# Input_v1_1.net
KiCad netlist of a schematic drawn in EAGLE
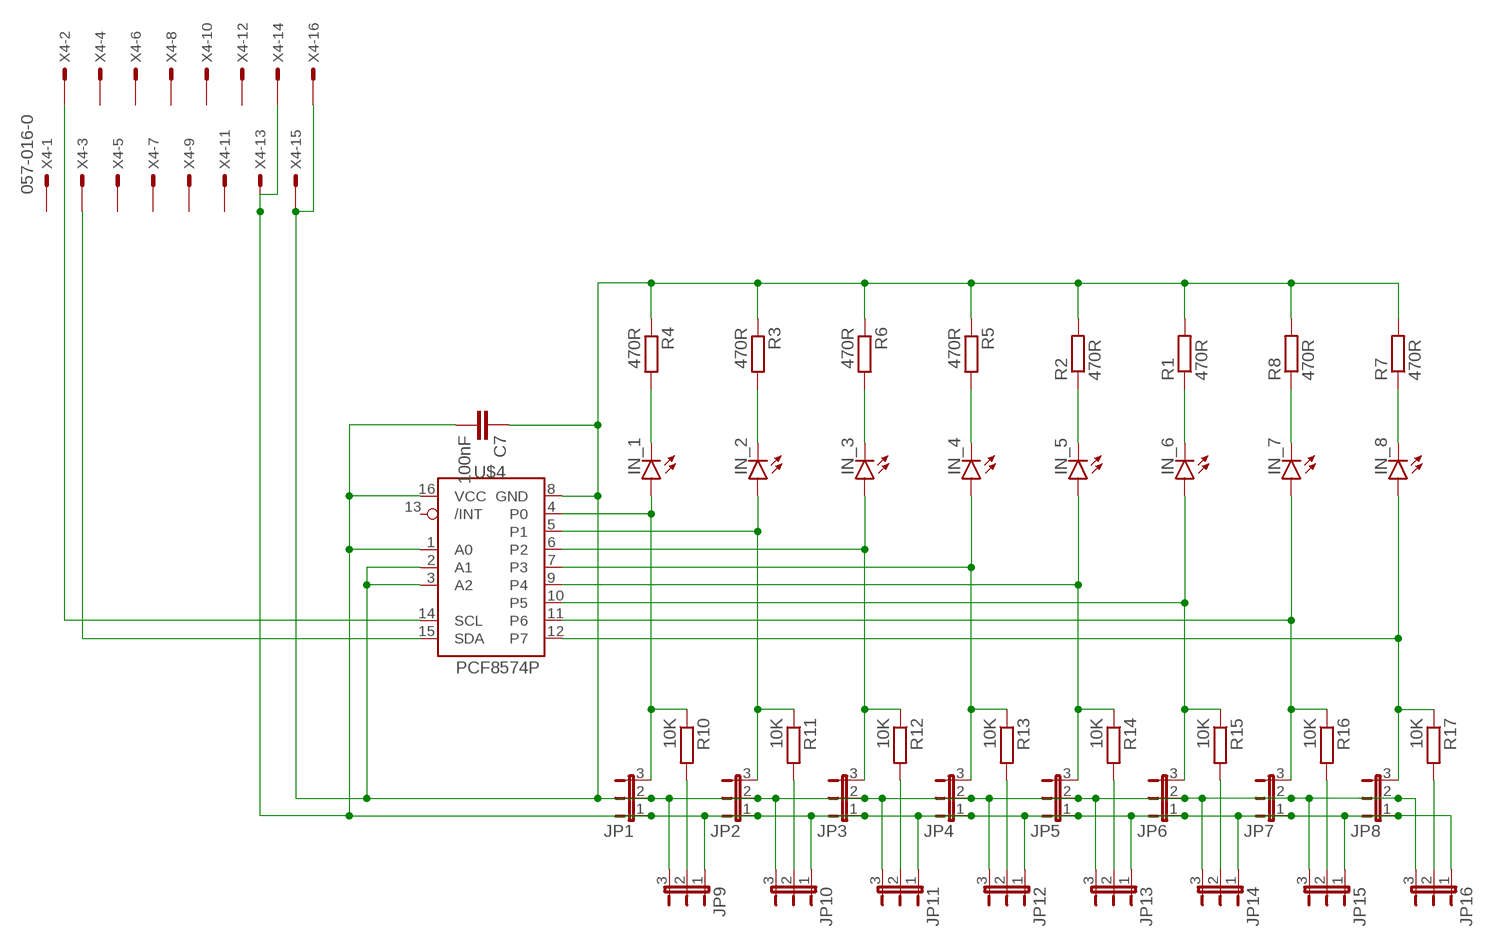
[diagram p0: schematic, sheet 1]

(export (version "E")
  (design (tool "Eeschema 10.0.6"))
  (components
    (comp (ref "C7")
      (value "100nF")
      (footprint "eagle-import:C025-024X044")
      (libsource (lib "eagle-import") (part "C-EU025-024X044"))
    )
    (comp (ref "IN_1")
      (value "LED3MM")
      (footprint "eagle-import:LED3MM")
      (libsource (lib "eagle-import") (part "LED3MM"))
    )
    (comp (ref "IN_2")
      (value "LED3MM")
      (footprint "eagle-import:LED3MM")
      (libsource (lib "eagle-import") (part "LED3MM"))
    )
    (comp (ref "IN_3")
      (value "LED3MM")
      (footprint "eagle-import:LED3MM")
      (libsource (lib "eagle-import") (part "LED3MM"))
    )
    (comp (ref "IN_4")
      (value "LED3MM")
      (footprint "eagle-import:LED3MM")
      (libsource (lib "eagle-import") (part "LED3MM"))
    )
    (comp (ref "IN_5")
      (value "LED3MM")
      (footprint "eagle-import:LED3MM")
      (libsource (lib "eagle-import") (part "LED3MM"))
    )
    (comp (ref "IN_6")
      (value "LED3MM")
      (footprint "eagle-import:LED3MM")
      (libsource (lib "eagle-import") (part "LED3MM"))
    )
    (comp (ref "IN_7")
      (value "LED3MM")
      (footprint "eagle-import:LED3MM")
      (libsource (lib "eagle-import") (part "LED3MM"))
    )
    (comp (ref "IN_8")
      (value "LED3MM")
      (footprint "eagle-import:LED3MM")
      (libsource (lib "eagle-import") (part "LED3MM"))
    )
    (comp (ref "JP1")
      (value "JP2E")
      (footprint "eagle-import:JP2")
      (libsource (lib "eagle-import") (part "JP2E"))
    )
    (comp (ref "JP2")
      (value "JP2E")
      (footprint "eagle-import:JP2")
      (libsource (lib "eagle-import") (part "JP2E"))
    )
    (comp (ref "JP3")
      (value "JP2E")
      (footprint "eagle-import:JP2")
      (libsource (lib "eagle-import") (part "JP2E"))
    )
    (comp (ref "JP4")
      (value "JP2E")
      (footprint "eagle-import:JP2")
      (libsource (lib "eagle-import") (part "JP2E"))
    )
    (comp (ref "JP5")
      (value "JP2E")
      (footprint "eagle-import:JP2")
      (libsource (lib "eagle-import") (part "JP2E"))
    )
    (comp (ref "JP6")
      (value "JP2E")
      (footprint "eagle-import:JP2")
      (libsource (lib "eagle-import") (part "JP2E"))
    )
    (comp (ref "JP7")
      (value "JP2E")
      (footprint "eagle-import:JP2")
      (libsource (lib "eagle-import") (part "JP2E"))
    )
    (comp (ref "JP8")
      (value "JP2E")
      (footprint "eagle-import:JP2")
      (libsource (lib "eagle-import") (part "JP2E"))
    )
    (comp (ref "JP9")
      (value "JP2E")
      (footprint "eagle-import:JP2")
      (libsource (lib "eagle-import") (part "JP2E"))
    )
    (comp (ref "JP10")
      (value "JP2E")
      (footprint "eagle-import:JP2")
      (libsource (lib "eagle-import") (part "JP2E"))
    )
    (comp (ref "JP11")
      (value "JP2E")
      (footprint "eagle-import:JP2")
      (libsource (lib "eagle-import") (part "JP2E"))
    )
    (comp (ref "JP12")
      (value "JP2E")
      (footprint "eagle-import:JP2")
      (libsource (lib "eagle-import") (part "JP2E"))
    )
    (comp (ref "JP13")
      (value "JP2E")
      (footprint "eagle-import:JP2")
      (libsource (lib "eagle-import") (part "JP2E"))
    )
    (comp (ref "JP14")
      (value "JP2E")
      (footprint "eagle-import:JP2")
      (libsource (lib "eagle-import") (part "JP2E"))
    )
    (comp (ref "JP15")
      (value "JP2E")
      (footprint "eagle-import:JP2")
      (libsource (lib "eagle-import") (part "JP2E"))
    )
    (comp (ref "JP16")
      (value "JP2E")
      (footprint "eagle-import:JP2")
      (libsource (lib "eagle-import") (part "JP2E"))
    )
    (comp (ref "R1")
      (value "470R")
      (footprint "eagle-import:0309_10")
      (libsource (lib "eagle-import") (part "R-EU_0309/10"))
    )
    (comp (ref "R2")
      (value "470R")
      (footprint "eagle-import:0309_10")
      (libsource (lib "eagle-import") (part "R-EU_0309/10"))
    )
    (comp (ref "R3")
      (value "470R")
      (footprint "eagle-import:0309_10")
      (libsource (lib "eagle-import") (part "R-EU_0309/10"))
    )
    (comp (ref "R4")
      (value "470R")
      (footprint "eagle-import:0309_10")
      (libsource (lib "eagle-import") (part "R-EU_0309/10"))
    )
    (comp (ref "R5")
      (value "470R")
      (footprint "eagle-import:0309_10")
      (libsource (lib "eagle-import") (part "R-EU_0309/10"))
    )
    (comp (ref "R6")
      (value "470R")
      (footprint "eagle-import:0309_10")
      (libsource (lib "eagle-import") (part "R-EU_0309/10"))
    )
    (comp (ref "R7")
      (value "470R")
      (footprint "eagle-import:0309_10")
      (libsource (lib "eagle-import") (part "R-EU_0309/10"))
    )
    (comp (ref "R8")
      (value "470R")
      (footprint "eagle-import:0309_10")
      (libsource (lib "eagle-import") (part "R-EU_0309/10"))
    )
    (comp (ref "R10")
      (value "10K")
      (footprint "eagle-import:0309_10")
      (libsource (lib "eagle-import") (part "R-EU_0309/10"))
    )
    (comp (ref "R11")
      (value "10K")
      (footprint "eagle-import:0309_10")
      (libsource (lib "eagle-import") (part "R-EU_0309/10"))
    )
    (comp (ref "R12")
      (value "10K")
      (footprint "eagle-import:0309_10")
      (libsource (lib "eagle-import") (part "R-EU_0309/10"))
    )
    (comp (ref "R13")
      (value "10K")
      (footprint "eagle-import:0309_10")
      (libsource (lib "eagle-import") (part "R-EU_0309/10"))
    )
    (comp (ref "R14")
      (value "10K")
      (footprint "eagle-import:0309_10")
      (libsource (lib "eagle-import") (part "R-EU_0309/10"))
    )
    (comp (ref "R15")
      (value "10K")
      (footprint "eagle-import:0309_10")
      (libsource (lib "eagle-import") (part "R-EU_0309/10"))
    )
    (comp (ref "R16")
      (value "10K")
      (footprint "eagle-import:0309_10")
      (libsource (lib "eagle-import") (part "R-EU_0309/10"))
    )
    (comp (ref "R17")
      (value "10K")
      (footprint "eagle-import:0309_10")
      (libsource (lib "eagle-import") (part "R-EU_0309/10"))
    )
    (comp (ref "U$4")
      (value "PCF8574P")
      (footprint "eagle-import:DIL16")
      (libsource (lib "eagle-import") (part "PCF8574P"))
    )
    (comp (ref "X4")
      (value "057-016-0")
      (footprint "eagle-import:057-016-0")
      (libsource (lib "eagle-import") (part "057-016-0"))
    )
  )
  (nets
    (net (code "1") (name "Net-(IN_1-C)") (class "Default")
      (node (ref "IN_1") (pin "K") (pinfunction "C_K") (pintype "passive"))
      (node (ref "R4") (pin "2") (pinfunction "2_2") (pintype "passive"))
    )
    (net (code "2") (name "Net-(IN_2-C)") (class "Default")
      (node (ref "IN_2") (pin "K") (pinfunction "C_K") (pintype "passive"))
      (node (ref "R3") (pin "2") (pinfunction "2_2") (pintype "passive"))
    )
    (net (code "3") (name "Net-(IN_3-C)") (class "Default")
      (node (ref "IN_3") (pin "K") (pinfunction "C_K") (pintype "passive"))
      (node (ref "R6") (pin "2") (pinfunction "2_2") (pintype "passive"))
    )
    (net (code "4") (name "Net-(IN_4-C)") (class "Default")
      (node (ref "IN_4") (pin "K") (pinfunction "C_K") (pintype "passive"))
      (node (ref "R5") (pin "2") (pinfunction "2_2") (pintype "passive"))
    )
    (net (code "5") (name "Net-(IN_5-C)") (class "Default")
      (node (ref "IN_5") (pin "K") (pinfunction "C_K") (pintype "passive"))
      (node (ref "R2") (pin "1") (pinfunction "1_1") (pintype "passive"))
    )
    (net (code "6") (name "Net-(IN_6-C)") (class "Default")
      (node (ref "IN_6") (pin "K") (pinfunction "C_K") (pintype "passive"))
      (node (ref "R1") (pin "1") (pinfunction "1_1") (pintype "passive"))
    )
    (net (code "7") (name "Net-(IN_7-C)") (class "Default")
      (node (ref "IN_7") (pin "K") (pinfunction "C_K") (pintype "passive"))
      (node (ref "R8") (pin "1") (pinfunction "1_1") (pintype "passive"))
    )
    (net (code "8") (name "Net-(IN_8-C)") (class "Default")
      (node (ref "IN_8") (pin "K") (pinfunction "C_K") (pintype "passive"))
      (node (ref "R7") (pin "1") (pinfunction "1_1") (pintype "passive"))
    )
    (net (code "9") (name "Net-(JP9-Pad2)") (class "Default")
      (node (ref "JP9") (pin "2") (pinfunction "2_2") (pintype "passive"))
      (node (ref "R10") (pin "2") (pinfunction "2_2") (pintype "passive"))
    )
    (net (code "10") (name "Net-(JP10-Pad2)") (class "Default")
      (node (ref "JP10") (pin "2") (pinfunction "2_2") (pintype "passive"))
      (node (ref "R11") (pin "2") (pinfunction "2_2") (pintype "passive"))
    )
    (net (code "11") (name "Net-(JP11-Pad2)") (class "Default")
      (node (ref "JP11") (pin "2") (pinfunction "2_2") (pintype "passive"))
      (node (ref "R12") (pin "2") (pinfunction "2_2") (pintype "passive"))
    )
    (net (code "12") (name "Net-(JP12-Pad2)") (class "Default")
      (node (ref "JP12") (pin "2") (pinfunction "2_2") (pintype "passive"))
      (node (ref "R13") (pin "2") (pinfunction "2_2") (pintype "passive"))
    )
    (net (code "13") (name "Net-(JP13-Pad2)") (class "Default")
      (node (ref "JP13") (pin "2") (pinfunction "2_2") (pintype "passive"))
      (node (ref "R14") (pin "2") (pinfunction "2_2") (pintype "passive"))
    )
    (net (code "14") (name "Net-(JP14-Pad2)") (class "Default")
      (node (ref "JP14") (pin "2") (pinfunction "2_2") (pintype "passive"))
      (node (ref "R15") (pin "2") (pinfunction "2_2") (pintype "passive"))
    )
    (net (code "15") (name "Net-(JP15-Pad2)") (class "Default")
      (node (ref "JP15") (pin "2") (pinfunction "2_2") (pintype "passive"))
      (node (ref "R16") (pin "2") (pinfunction "2_2") (pintype "passive"))
    )
    (net (code "16") (name "Net-(JP16-Pad2)") (class "Default")
      (node (ref "JP16") (pin "2") (pinfunction "2_2") (pintype "passive"))
      (node (ref "R17") (pin "2") (pinfunction "2_2") (pintype "passive"))
    )
    (net (code "17") (name "Net-(U$4-A0)") (class "Default")
      (node (ref "C7") (pin "2") (pinfunction "2_2") (pintype "passive"))
      (node (ref "JP1") (pin "1") (pinfunction "1_1") (pintype "passive"))
      (node (ref "JP10") (pin "1") (pinfunction "1_1") (pintype "passive"))
      (node (ref "JP11") (pin "1") (pinfunction "1_1") (pintype "passive"))
      (node (ref "JP12") (pin "1") (pinfunction "1_1") (pintype "passive"))
      (node (ref "JP13") (pin "1") (pinfunction "1_1") (pintype "passive"))
      (node (ref "JP14") (pin "1") (pinfunction "1_1") (pintype "passive"))
      (node (ref "JP15") (pin "1") (pinfunction "1_1") (pintype "passive"))
      (node (ref "JP16") (pin "1") (pinfunction "1_1") (pintype "passive"))
      (node (ref "JP2") (pin "1") (pinfunction "1_1") (pintype "passive"))
      (node (ref "JP3") (pin "1") (pinfunction "1_1") (pintype "passive"))
      (node (ref "JP4") (pin "1") (pinfunction "1_1") (pintype "passive"))
      (node (ref "JP5") (pin "1") (pinfunction "1_1") (pintype "passive"))
      (node (ref "JP6") (pin "1") (pinfunction "1_1") (pintype "passive"))
      (node (ref "JP7") (pin "1") (pinfunction "1_1") (pintype "passive"))
      (node (ref "JP8") (pin "1") (pinfunction "1_1") (pintype "passive"))
      (node (ref "JP9") (pin "1") (pinfunction "1_1") (pintype "passive"))
      (node (ref "U$4") (pin "1") (pinfunction "A0_1") (pintype "input"))
      (node (ref "U$4") (pin "16") (pinfunction "VCC_16") (pintype "power_in"))
      (node (ref "X4") (pin "13") (pinfunction "S_13") (pintype "passive"))
      (node (ref "X4") (pin "14") (pinfunction "S_14") (pintype "passive"))
    )
    (net (code "18") (name "Net-(U$4-A1)") (class "Default")
      (node (ref "C7") (pin "1") (pinfunction "1_1") (pintype "passive"))
      (node (ref "JP1") (pin "2") (pinfunction "2_2") (pintype "passive"))
      (node (ref "JP10") (pin "3") (pinfunction "3_3") (pintype "passive"))
      (node (ref "JP11") (pin "3") (pinfunction "3_3") (pintype "passive"))
      (node (ref "JP12") (pin "3") (pinfunction "3_3") (pintype "passive"))
      (node (ref "JP13") (pin "3") (pinfunction "3_3") (pintype "passive"))
      (node (ref "JP14") (pin "3") (pinfunction "3_3") (pintype "passive"))
      (node (ref "JP15") (pin "3") (pinfunction "3_3") (pintype "passive"))
      (node (ref "JP16") (pin "3") (pinfunction "3_3") (pintype "passive"))
      (node (ref "JP2") (pin "2") (pinfunction "2_2") (pintype "passive"))
      (node (ref "JP3") (pin "2") (pinfunction "2_2") (pintype "passive"))
      (node (ref "JP4") (pin "2") (pinfunction "2_2") (pintype "passive"))
      (node (ref "JP5") (pin "2") (pinfunction "2_2") (pintype "passive"))
      (node (ref "JP6") (pin "2") (pinfunction "2_2") (pintype "passive"))
      (node (ref "JP7") (pin "2") (pinfunction "2_2") (pintype "passive"))
      (node (ref "JP8") (pin "2") (pinfunction "2_2") (pintype "passive"))
      (node (ref "JP9") (pin "3") (pinfunction "3_3") (pintype "passive"))
      (node (ref "R1") (pin "2") (pinfunction "2_2") (pintype "passive"))
      (node (ref "R2") (pin "2") (pinfunction "2_2") (pintype "passive"))
      (node (ref "R3") (pin "1") (pinfunction "1_1") (pintype "passive"))
      (node (ref "R4") (pin "1") (pinfunction "1_1") (pintype "passive"))
      (node (ref "R5") (pin "1") (pinfunction "1_1") (pintype "passive"))
      (node (ref "R6") (pin "1") (pinfunction "1_1") (pintype "passive"))
      (node (ref "R7") (pin "2") (pinfunction "2_2") (pintype "passive"))
      (node (ref "R8") (pin "2") (pinfunction "2_2") (pintype "passive"))
      (node (ref "U$4") (pin "2") (pinfunction "A1_2") (pintype "input"))
      (node (ref "U$4") (pin "3") (pinfunction "A2_3") (pintype "input"))
      (node (ref "U$4") (pin "8") (pinfunction "GND_8") (pintype "power_in"))
      (node (ref "X4") (pin "15") (pinfunction "S_15") (pintype "passive"))
      (node (ref "X4") (pin "16") (pinfunction "S_16") (pintype "passive"))
    )
    (net (code "19") (name "Net-(U$4-P0)") (class "Default")
      (node (ref "IN_1") (pin "A") (pinfunction "A_A") (pintype "passive"))
      (node (ref "JP1") (pin "3") (pinfunction "3_3") (pintype "passive"))
      (node (ref "R10") (pin "1") (pinfunction "1_1") (pintype "passive"))
      (node (ref "U$4") (pin "4") (pinfunction "P0_4") (pintype "bidirectional"))
    )
    (net (code "20") (name "Net-(U$4-P1)") (class "Default")
      (node (ref "IN_2") (pin "A") (pinfunction "A_A") (pintype "passive"))
      (node (ref "JP2") (pin "3") (pinfunction "3_3") (pintype "passive"))
      (node (ref "R11") (pin "1") (pinfunction "1_1") (pintype "passive"))
      (node (ref "U$4") (pin "5") (pinfunction "P1_5") (pintype "bidirectional"))
    )
    (net (code "21") (name "Net-(U$4-P2)") (class "Default")
      (node (ref "IN_3") (pin "A") (pinfunction "A_A") (pintype "passive"))
      (node (ref "JP3") (pin "3") (pinfunction "3_3") (pintype "passive"))
      (node (ref "R12") (pin "1") (pinfunction "1_1") (pintype "passive"))
      (node (ref "U$4") (pin "6") (pinfunction "P2_6") (pintype "bidirectional"))
    )
    (net (code "22") (name "Net-(U$4-P3)") (class "Default")
      (node (ref "IN_4") (pin "A") (pinfunction "A_A") (pintype "passive"))
      (node (ref "JP4") (pin "3") (pinfunction "3_3") (pintype "passive"))
      (node (ref "R13") (pin "1") (pinfunction "1_1") (pintype "passive"))
      (node (ref "U$4") (pin "7") (pinfunction "P3_7") (pintype "bidirectional"))
    )
    (net (code "23") (name "Net-(U$4-P4)") (class "Default")
      (node (ref "IN_5") (pin "A") (pinfunction "A_A") (pintype "passive"))
      (node (ref "JP5") (pin "3") (pinfunction "3_3") (pintype "passive"))
      (node (ref "R14") (pin "1") (pinfunction "1_1") (pintype "passive"))
      (node (ref "U$4") (pin "9") (pinfunction "P4_9") (pintype "bidirectional"))
    )
    (net (code "24") (name "Net-(U$4-P5)") (class "Default")
      (node (ref "IN_6") (pin "A") (pinfunction "A_A") (pintype "passive"))
      (node (ref "JP6") (pin "3") (pinfunction "3_3") (pintype "passive"))
      (node (ref "R15") (pin "1") (pinfunction "1_1") (pintype "passive"))
      (node (ref "U$4") (pin "10") (pinfunction "P5_10") (pintype "bidirectional"))
    )
    (net (code "25") (name "Net-(U$4-P6)") (class "Default")
      (node (ref "IN_7") (pin "A") (pinfunction "A_A") (pintype "passive"))
      (node (ref "JP7") (pin "3") (pinfunction "3_3") (pintype "passive"))
      (node (ref "R16") (pin "1") (pinfunction "1_1") (pintype "passive"))
      (node (ref "U$4") (pin "11") (pinfunction "P6_11") (pintype "bidirectional"))
    )
    (net (code "26") (name "Net-(U$4-P7)") (class "Default")
      (node (ref "IN_8") (pin "A") (pinfunction "A_A") (pintype "passive"))
      (node (ref "JP8") (pin "3") (pinfunction "3_3") (pintype "passive"))
      (node (ref "R17") (pin "1") (pinfunction "1_1") (pintype "passive"))
      (node (ref "U$4") (pin "12") (pinfunction "P7_12") (pintype "bidirectional"))
    )
    (net (code "27") (name "Net-(U$4-SCL)") (class "Default")
      (node (ref "U$4") (pin "14") (pinfunction "SCL_14") (pintype "input"))
      (node (ref "X4") (pin "2") (pinfunction "S_2") (pintype "passive"))
    )
    (net (code "28") (name "Net-(U$4-SDA)") (class "Default")
      (node (ref "U$4") (pin "15") (pinfunction "SDA_15") (pintype "bidirectional"))
      (node (ref "X4") (pin "3") (pinfunction "S_3") (pintype "passive"))
    )
    (net (code "29") (name "unconnected-(U$4-{slash}INT-Pad13)") (class "Default")
      (node (ref "U$4") (pin "13") (pinfunction "/INT_13") (pintype "output"))
    )
    (net (code "30") (name "unconnected-(X4A-S-Pad1)") (class "Default")
      (node (ref "X4") (pin "1") (pinfunction "S_1") (pintype "passive"))
    )
    (net (code "31") (name "unconnected-(X4B-S-Pad10)") (class "Default")
      (node (ref "X4") (pin "10") (pinfunction "S_10") (pintype "passive"))
    )
    (net (code "32") (name "unconnected-(X4C-S-Pad11)") (class "Default")
      (node (ref "X4") (pin "11") (pinfunction "S_11") (pintype "passive"))
    )
    (net (code "33") (name "unconnected-(X4D-S-Pad12)") (class "Default")
      (node (ref "X4") (pin "12") (pinfunction "S_12") (pintype "passive"))
    )
    (net (code "34") (name "unconnected-(X4K-S-Pad4)") (class "Default")
      (node (ref "X4") (pin "4") (pinfunction "S_4") (pintype "passive"))
    )
    (net (code "35") (name "unconnected-(X4L-S-Pad5)") (class "Default")
      (node (ref "X4") (pin "5") (pinfunction "S_5") (pintype "passive"))
    )
    (net (code "36") (name "unconnected-(X4M-S-Pad6)") (class "Default")
      (node (ref "X4") (pin "6") (pinfunction "S_6") (pintype "passive"))
    )
    (net (code "37") (name "unconnected-(X4N-S-Pad7)") (class "Default")
      (node (ref "X4") (pin "7") (pinfunction "S_7") (pintype "passive"))
    )
    (net (code "38") (name "unconnected-(X4O-S-Pad8)") (class "Default")
      (node (ref "X4") (pin "8") (pinfunction "S_8") (pintype "passive"))
    )
    (net (code "39") (name "unconnected-(X4P-S-Pad9)") (class "Default")
      (node (ref "X4") (pin "9") (pinfunction "S_9") (pintype "passive"))
    )
  )
)
